# 1.net
KiCad netlist of a schematic drawn in EAGLE
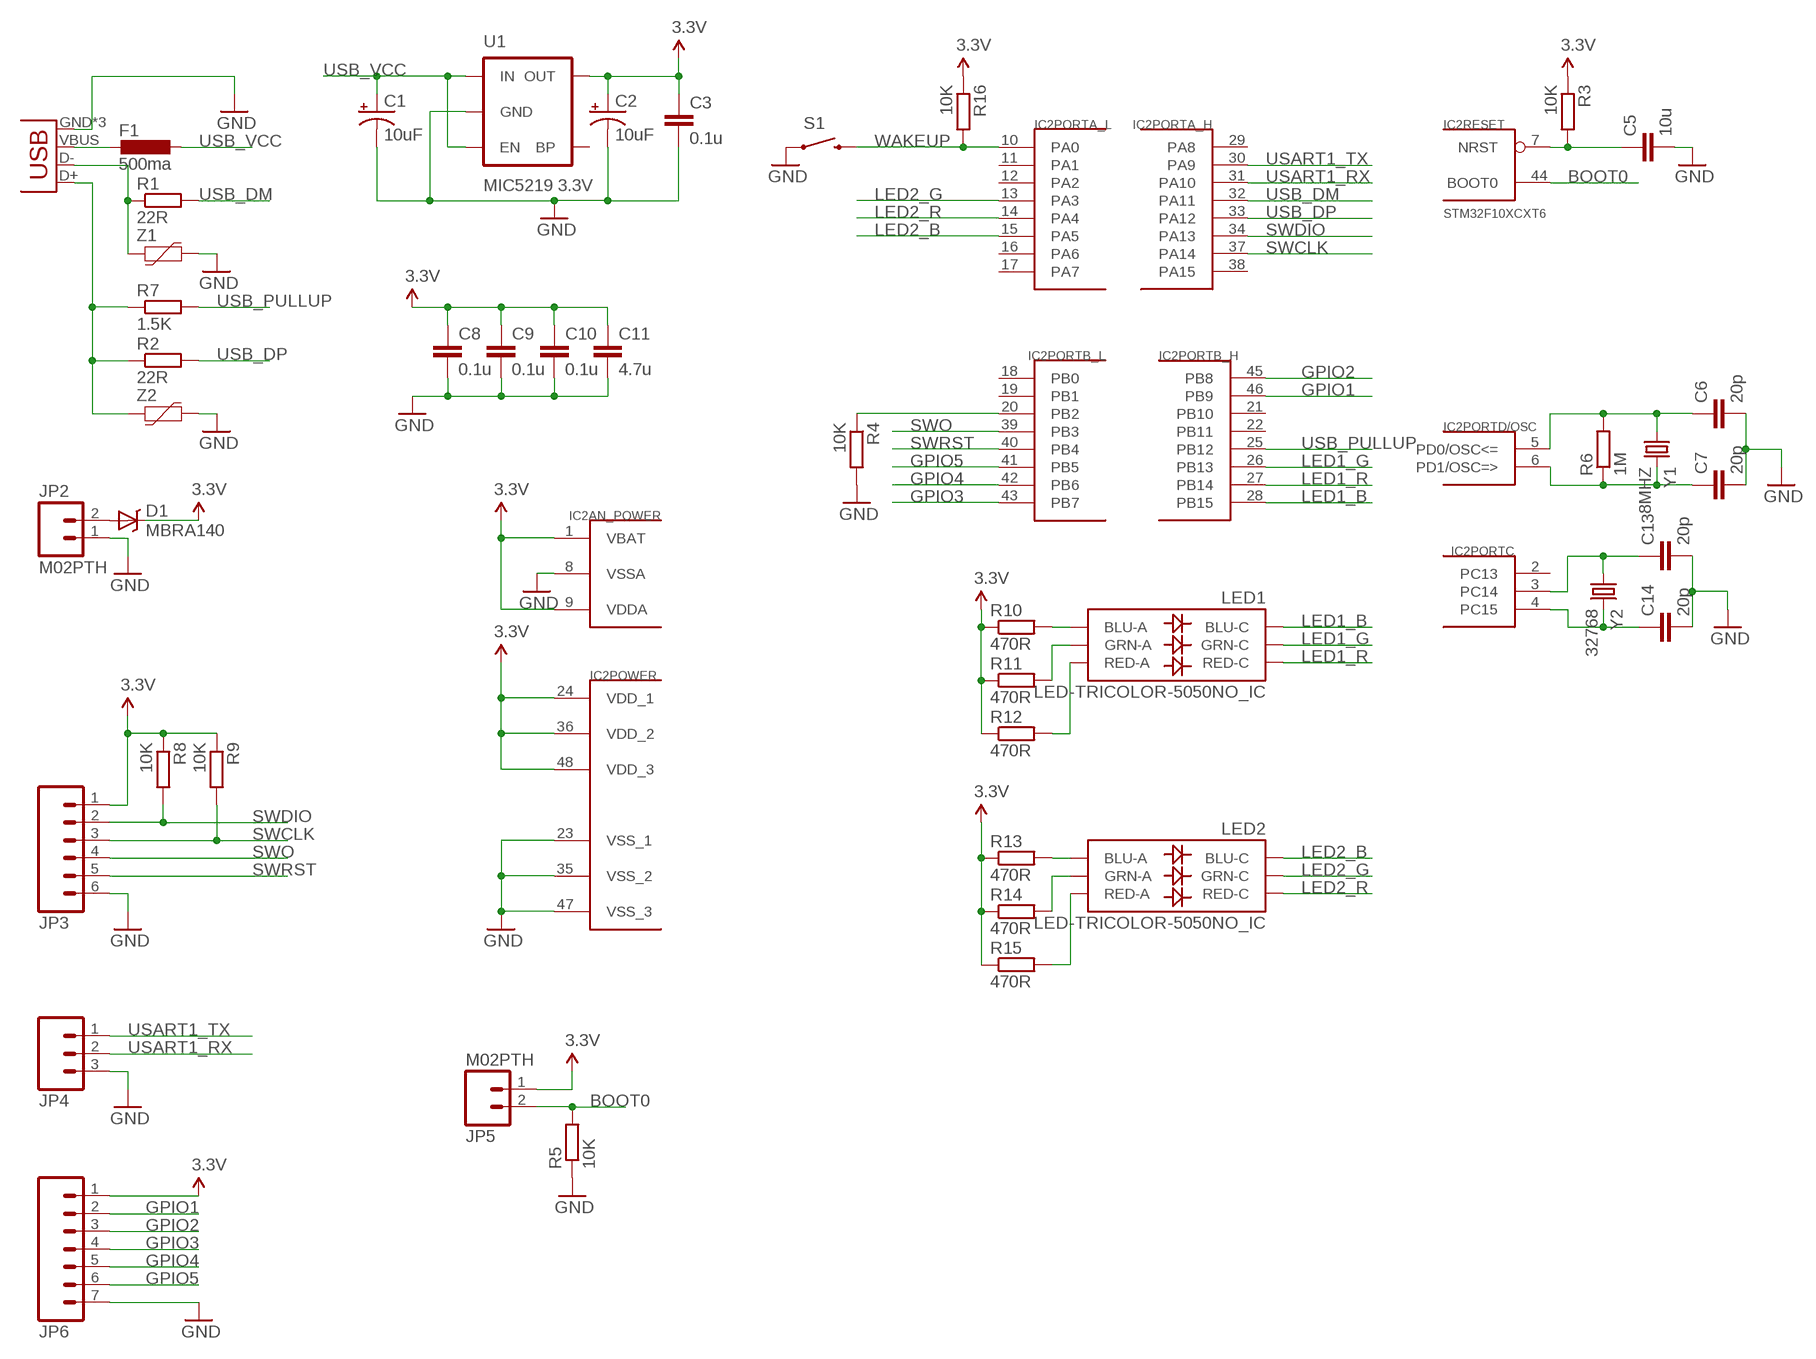
[diagram p0: schematic, sheet 1]

(export (version "E")
  (design (tool "Eeschema 10.0.6"))
  (components
    (comp (ref "C1")
      (value "10uF")
      (footprint "eagle-import:EIA3216")
      (libsource (lib "eagle-import") (part "10UF-TANT"))
    )
    (comp (ref "C2")
      (value "10uF")
      (footprint "eagle-import:EIA3216")
      (libsource (lib "eagle-import") (part "10UF-TANT"))
    )
    (comp (ref "C3")
      (value "0.1u")
      (footprint "eagle-import:C0603K")
      (libsource (lib "eagle-import") (part "C-EUC0603K"))
    )
    (comp (ref "C5")
      (value "10u")
      (footprint "eagle-import:C0603K")
      (libsource (lib "eagle-import") (part "C-EUC0603K"))
    )
    (comp (ref "C6")
      (value "20p")
      (footprint "eagle-import:C0603K")
      (libsource (lib "eagle-import") (part "C-EUC0603K"))
    )
    (comp (ref "C7")
      (value "20p")
      (footprint "eagle-import:C0603K")
      (libsource (lib "eagle-import") (part "C-EUC0603K"))
    )
    (comp (ref "C8")
      (value "0.1u")
      (footprint "eagle-import:C0603K")
      (libsource (lib "eagle-import") (part "C-EUC0603K"))
    )
    (comp (ref "C9")
      (value "0.1u")
      (footprint "eagle-import:C0603K")
      (libsource (lib "eagle-import") (part "C-EUC0603K"))
    )
    (comp (ref "C10")
      (value "0.1u")
      (footprint "eagle-import:C0603K")
      (libsource (lib "eagle-import") (part "C-EUC0603K"))
    )
    (comp (ref "C11")
      (value "4.7u")
      (footprint "eagle-import:C0603K")
      (libsource (lib "eagle-import") (part "C-EUC0603K"))
    )
    (comp (ref "C13")
      (value "20p")
      (footprint "eagle-import:C0603K")
      (libsource (lib "eagle-import") (part "C-EUC0603K"))
    )
    (comp (ref "C14")
      (value "20p")
      (footprint "eagle-import:C0603K")
      (libsource (lib "eagle-import") (part "C-EUC0603K"))
    )
    (comp (ref "D1")
      (value "MBRA140")
      (footprint "eagle-import:SMA-DIODE")
      (libsource (lib "eagle-import") (part "MBRA140"))
    )
    (comp (ref "F1")
      (value "500ma")
      (footprint "eagle-import:L2012C")
      (libsource (lib "eagle-import") (part "L-EUL2012C"))
    )
    (comp (ref "IC2")
      (value "STM32F10XCXT6")
      (footprint "eagle-import:TQFP48")
      (libsource (lib "eagle-import") (part "STM32F10XCXT6"))
    )
    (comp (ref "JP1")
      (value "USB-MICROB")
      (footprint "eagle-import:USB-MICROB")
      (libsource (lib "eagle-import") (part "USB-MICROB"))
    )
    (comp (ref "JP2")
      (value "M02PTH")
      (footprint "eagle-import:1X02")
      (libsource (lib "eagle-import") (part "M02PTH"))
    )
    (comp (ref "JP3")
      (value "M06SIP")
      (footprint "eagle-import:1X06")
      (libsource (lib "eagle-import") (part "M06SIP"))
    )
    (comp (ref "JP4")
      (value "M03PTH")
      (footprint "eagle-import:1X03")
      (libsource (lib "eagle-import") (part "M03PTH"))
    )
    (comp (ref "JP5")
      (value "M02PTH")
      (footprint "eagle-import:1X02")
      (libsource (lib "eagle-import") (part "M02PTH"))
    )
    (comp (ref "JP6")
      (value "M07")
      (footprint "eagle-import:1X07")
      (libsource (lib "eagle-import") (part "M07"))
    )
    (comp (ref "LED1")
      (value "LED-TRICOLOR-5050NO_IC")
      (footprint "eagle-import:LED-TRICOLOR-5050")
      (libsource (lib "eagle-import") (part "LED-TRICOLOR-5050NO_IC"))
    )
    (comp (ref "LED2")
      (value "LED-TRICOLOR-5050NO_IC")
      (footprint "eagle-import:LED-TRICOLOR-5050")
      (libsource (lib "eagle-import") (part "LED-TRICOLOR-5050NO_IC"))
    )
    (comp (ref "R1")
      (value "22R")
      (footprint "eagle-import:R0603")
      (libsource (lib "eagle-import") (part "R-EU_R0603"))
    )
    (comp (ref "R2")
      (value "22R")
      (footprint "eagle-import:R0603")
      (libsource (lib "eagle-import") (part "R-EU_R0603"))
    )
    (comp (ref "R3")
      (value "10K")
      (footprint "eagle-import:R0603")
      (libsource (lib "eagle-import") (part "R-EU_R0603"))
    )
    (comp (ref "R4")
      (value "10K")
      (footprint "eagle-import:R0603")
      (libsource (lib "eagle-import") (part "R-EU_R0603"))
    )
    (comp (ref "R5")
      (value "10K")
      (footprint "eagle-import:R0603")
      (libsource (lib "eagle-import") (part "R-EU_R0603"))
    )
    (comp (ref "R6")
      (value "1M")
      (footprint "eagle-import:R0603")
      (libsource (lib "eagle-import") (part "R-EU_R0603"))
    )
    (comp (ref "R7")
      (value "1.5K")
      (footprint "eagle-import:R0603")
      (libsource (lib "eagle-import") (part "R-EU_R0603"))
    )
    (comp (ref "R8")
      (value "10K")
      (footprint "eagle-import:R0603")
      (libsource (lib "eagle-import") (part "R-EU_R0603"))
    )
    (comp (ref "R9")
      (value "10K")
      (footprint "eagle-import:R0603")
      (libsource (lib "eagle-import") (part "R-EU_R0603"))
    )
    (comp (ref "R10")
      (value "470R")
      (footprint "eagle-import:R0603")
      (libsource (lib "eagle-import") (part "R-EU_R0603"))
    )
    (comp (ref "R11")
      (value "470R")
      (footprint "eagle-import:R0603")
      (libsource (lib "eagle-import") (part "R-EU_R0603"))
    )
    (comp (ref "R12")
      (value "470R")
      (footprint "eagle-import:R0603")
      (libsource (lib "eagle-import") (part "R-EU_R0603"))
    )
    (comp (ref "R13")
      (value "470R")
      (footprint "eagle-import:R0603")
      (libsource (lib "eagle-import") (part "R-EU_R0603"))
    )
    (comp (ref "R14")
      (value "470R")
      (footprint "eagle-import:R0603")
      (libsource (lib "eagle-import") (part "R-EU_R0603"))
    )
    (comp (ref "R15")
      (value "470R")
      (footprint "eagle-import:R0603")
      (libsource (lib "eagle-import") (part "R-EU_R0603"))
    )
    (comp (ref "R16")
      (value "10K")
      (footprint "eagle-import:R0603")
      (libsource (lib "eagle-import") (part "R-EU_R0603"))
    )
    (comp (ref "S1")
      (value "SWITCH-MOMENTARY-2SMD-4")
      (footprint "eagle-import:TACTILE_SWITCH_TALL")
      (libsource (lib "eagle-import") (part "SWITCH-MOMENTARY-2SMD-4"))
    )
    (comp (ref "U1")
      (value "MIC5219 3.3V")
      (footprint "eagle-import:SOT23-5")
      (libsource (lib "eagle-import") (part "V_REG_MIC52193.3V"))
    )
    (comp (ref "Y1")
      (value "8MHZ")
      (footprint "eagle-import:CRYSTAL-SMD-5X3")
      (libsource (lib "eagle-import") (part "CRYSTAL5X3"))
    )
    (comp (ref "Y2")
      (value "32768")
      (footprint "eagle-import:CRYSTAL-32KHZ-SMD_EPSON_MC146")
      (libsource (lib "eagle-import") (part "CRYSTALEPSONMC146"))
    )
    (comp (ref "Z1")
      (value "VARISTOR-0603")
      (footprint "eagle-import:0603-RES")
      (libsource (lib "eagle-import") (part "VARISTOR-0603"))
    )
    (comp (ref "Z2")
      (value "VARISTOR-0603")
      (footprint "eagle-import:0603-RES")
      (libsource (lib "eagle-import") (part "VARISTOR-0603"))
    )
  )
  (nets
    (net (code "1") (name "/BOOT0") (class "Default")
      (node (ref "IC2") (pin "44") (pinfunction "BOOT0_44") (pintype "input"))
      (node (ref "JP5") (pin "2") (pinfunction "2_2") (pintype "passive"))
      (node (ref "R5") (pin "2") (pinfunction "2_2") (pintype "passive"))
    )
    (net (code "2") (name "/GPIO1") (class "Default")
      (node (ref "IC2") (pin "46") (pinfunction "PB9_46") (pintype "bidirectional"))
      (node (ref "JP6") (pin "2") (pinfunction "2_2") (pintype "passive"))
    )
    (net (code "3") (name "/GPIO2") (class "Default")
      (node (ref "IC2") (pin "45") (pinfunction "PB8_45") (pintype "bidirectional"))
      (node (ref "JP6") (pin "3") (pinfunction "3_3") (pintype "passive"))
    )
    (net (code "4") (name "/GPIO3") (class "Default")
      (node (ref "IC2") (pin "43") (pinfunction "PB7_43") (pintype "bidirectional"))
      (node (ref "JP6") (pin "4") (pinfunction "4_4") (pintype "passive"))
    )
    (net (code "5") (name "/GPIO4") (class "Default")
      (node (ref "IC2") (pin "42") (pinfunction "PB6_42") (pintype "bidirectional"))
      (node (ref "JP6") (pin "5") (pinfunction "5_5") (pintype "passive"))
    )
    (net (code "6") (name "/GPIO5") (class "Default")
      (node (ref "IC2") (pin "41") (pinfunction "PB5_41") (pintype "bidirectional"))
      (node (ref "JP6") (pin "6") (pinfunction "6_6") (pintype "passive"))
    )
    (net (code "7") (name "/LED1_B") (class "Default")
      (node (ref "IC2") (pin "28") (pinfunction "PB15_28") (pintype "bidirectional"))
      (node (ref "LED1") (pin "4") (pinfunction "BLU-C_4") (pintype "bidirectional"))
    )
    (net (code "8") (name "/LED1_G") (class "Default")
      (node (ref "IC2") (pin "26") (pinfunction "PB13_26") (pintype "bidirectional"))
      (node (ref "LED1") (pin "6") (pinfunction "GRN-C_6") (pintype "bidirectional"))
    )
    (net (code "9") (name "/LED1_R") (class "Default")
      (node (ref "IC2") (pin "27") (pinfunction "PB14_27") (pintype "bidirectional"))
      (node (ref "LED1") (pin "5") (pinfunction "RED-C_5") (pintype "bidirectional"))
    )
    (net (code "10") (name "/LED2_B") (class "Default")
      (node (ref "IC2") (pin "15") (pinfunction "PA5_15") (pintype "bidirectional"))
      (node (ref "LED2") (pin "4") (pinfunction "BLU-C_4") (pintype "bidirectional"))
    )
    (net (code "11") (name "/LED2_G") (class "Default")
      (node (ref "IC2") (pin "13") (pinfunction "PA3_13") (pintype "bidirectional"))
      (node (ref "LED2") (pin "6") (pinfunction "GRN-C_6") (pintype "bidirectional"))
    )
    (net (code "12") (name "/LED2_R") (class "Default")
      (node (ref "IC2") (pin "14") (pinfunction "PA4_14") (pintype "bidirectional"))
      (node (ref "LED2") (pin "5") (pinfunction "RED-C_5") (pintype "bidirectional"))
    )
    (net (code "13") (name "/SWCLK") (class "Default")
      (node (ref "IC2") (pin "37") (pinfunction "PA14_37") (pintype "bidirectional"))
      (node (ref "JP3") (pin "3") (pinfunction "3_3") (pintype "passive"))
      (node (ref "R9") (pin "2") (pinfunction "2_2") (pintype "passive"))
    )
    (net (code "14") (name "/SWDIO") (class "Default")
      (node (ref "IC2") (pin "34") (pinfunction "PA13_34") (pintype "bidirectional"))
      (node (ref "JP3") (pin "2") (pinfunction "2_2") (pintype "passive"))
      (node (ref "R8") (pin "2") (pinfunction "2_2") (pintype "passive"))
    )
    (net (code "15") (name "/SWO") (class "Default")
      (node (ref "IC2") (pin "39") (pinfunction "PB3_39") (pintype "bidirectional"))
      (node (ref "JP3") (pin "4") (pinfunction "4_4") (pintype "passive"))
    )
    (net (code "16") (name "/SWRST") (class "Default")
      (node (ref "IC2") (pin "40") (pinfunction "PB4_40") (pintype "bidirectional"))
      (node (ref "JP3") (pin "5") (pinfunction "5_5") (pintype "passive"))
    )
    (net (code "17") (name "/USART1_RX") (class "Default")
      (node (ref "IC2") (pin "31") (pinfunction "PA10_31") (pintype "bidirectional"))
      (node (ref "JP4") (pin "2") (pinfunction "2_2") (pintype "passive"))
    )
    (net (code "18") (name "/USART1_TX") (class "Default")
      (node (ref "IC2") (pin "30") (pinfunction "PA9_30") (pintype "bidirectional"))
      (node (ref "JP4") (pin "1") (pinfunction "1_1") (pintype "passive"))
    )
    (net (code "19") (name "/USB_DM") (class "Default")
      (node (ref "IC2") (pin "32") (pinfunction "PA11_32") (pintype "bidirectional"))
      (node (ref "R1") (pin "2") (pinfunction "2_2") (pintype "passive"))
    )
    (net (code "20") (name "/USB_DP") (class "Default")
      (node (ref "IC2") (pin "33") (pinfunction "PA12_33") (pintype "bidirectional"))
      (node (ref "R2") (pin "2") (pinfunction "2_2") (pintype "passive"))
    )
    (net (code "21") (name "/USB_PULLUP") (class "Default")
      (node (ref "IC2") (pin "25") (pinfunction "PB12_25") (pintype "bidirectional"))
      (node (ref "R7") (pin "2") (pinfunction "2_2") (pintype "passive"))
    )
    (net (code "22") (name "/USB_VCC") (class "Default")
      (node (ref "C1") (pin "A") (pinfunction "+_A") (pintype "passive"))
      (node (ref "F1") (pin "1") (pinfunction "1_1") (pintype "passive"))
      (node (ref "U1") (pin "1") (pinfunction "IN_1") (pintype "input"))
      (node (ref "U1") (pin "3") (pinfunction "EN_3") (pintype "input"))
    )
    (net (code "23") (name "/WAKEUP") (class "Default")
      (node (ref "IC2") (pin "10") (pinfunction "PA0_10") (pintype "bidirectional"))
      (node (ref "R16") (pin "2") (pinfunction "2_2") (pintype "passive"))
      (node (ref "S1") (pin "B2") (pinfunction "2_B2") (pintype "passive"))
    )
    (net (code "24") (name "3.3V") (class "Default")
      (node (ref "C10") (pin "1") (pinfunction "1_1") (pintype "passive"))
      (node (ref "C11") (pin "1") (pinfunction "1_1") (pintype "passive"))
      (node (ref "C2") (pin "A") (pinfunction "+_A") (pintype "passive"))
      (node (ref "C3") (pin "1") (pinfunction "1_1") (pintype "passive"))
      (node (ref "C8") (pin "1") (pinfunction "1_1") (pintype "passive"))
      (node (ref "C9") (pin "1") (pinfunction "1_1") (pintype "passive"))
      (node (ref "D1") (pin "C") (pinfunction "C_C") (pintype "passive"))
      (node (ref "IC2") (pin "1") (pinfunction "VBAT_1") (pintype "power_in"))
      (node (ref "IC2") (pin "24") (pinfunction "VDD_1_24") (pintype "power_in"))
      (node (ref "IC2") (pin "36") (pinfunction "VDD_2_36") (pintype "power_in"))
      (node (ref "IC2") (pin "48") (pinfunction "VDD_3_48") (pintype "power_in"))
      (node (ref "IC2") (pin "9") (pinfunction "VDDA_9") (pintype "power_in"))
      (node (ref "JP3") (pin "1") (pinfunction "1_1") (pintype "passive"))
      (node (ref "JP5") (pin "1") (pinfunction "1_1") (pintype "passive"))
      (node (ref "JP6") (pin "1") (pinfunction "1_1") (pintype "passive"))
      (node (ref "R10") (pin "1") (pinfunction "1_1") (pintype "passive"))
      (node (ref "R11") (pin "1") (pinfunction "1_1") (pintype "passive"))
      (node (ref "R12") (pin "1") (pinfunction "1_1") (pintype "passive"))
      (node (ref "R13") (pin "1") (pinfunction "1_1") (pintype "passive"))
      (node (ref "R14") (pin "1") (pinfunction "1_1") (pintype "passive"))
      (node (ref "R15") (pin "1") (pinfunction "1_1") (pintype "passive"))
      (node (ref "R16") (pin "1") (pinfunction "1_1") (pintype "passive"))
      (node (ref "R3") (pin "1") (pinfunction "1_1") (pintype "passive"))
      (node (ref "R8") (pin "1") (pinfunction "1_1") (pintype "passive"))
      (node (ref "R9") (pin "1") (pinfunction "1_1") (pintype "passive"))
      (node (ref "U1") (pin "5") (pinfunction "OUT_5") (pintype "passive"))
    )
    (net (code "25") (name "GND") (class "Default")
      (node (ref "C1") (pin "C") (pinfunction "-_C") (pintype "passive"))
      (node (ref "C10") (pin "2") (pinfunction "2_2") (pintype "passive"))
      (node (ref "C11") (pin "2") (pinfunction "2_2") (pintype "passive"))
      (node (ref "C13") (pin "2") (pinfunction "2_2") (pintype "passive"))
      (node (ref "C14") (pin "2") (pinfunction "2_2") (pintype "passive"))
      (node (ref "C2") (pin "C") (pinfunction "-_C") (pintype "passive"))
      (node (ref "C3") (pin "2") (pinfunction "2_2") (pintype "passive"))
      (node (ref "C5") (pin "2") (pinfunction "2_2") (pintype "passive"))
      (node (ref "C6") (pin "2") (pinfunction "2_2") (pintype "passive"))
      (node (ref "C7") (pin "2") (pinfunction "2_2") (pintype "passive"))
      (node (ref "C8") (pin "2") (pinfunction "2_2") (pintype "passive"))
      (node (ref "C9") (pin "2") (pinfunction "2_2") (pintype "passive"))
      (node (ref "IC2") (pin "23") (pinfunction "VSS_1_23") (pintype "power_in"))
      (node (ref "IC2") (pin "35") (pinfunction "VSS_2_35") (pintype "power_in"))
      (node (ref "IC2") (pin "47") (pinfunction "VSS_3_47") (pintype "power_in"))
      (node (ref "IC2") (pin "8") (pinfunction "VSSA_8") (pintype "power_in"))
      (node (ref "JP1") (pin "GND") (pinfunction "GND_GND") (pintype "bidirectional"))
      (node (ref "JP1") (pin "MT1") (pinfunction "GND_MT1") (pintype "bidirectional"))
      (node (ref "JP1") (pin "MT2") (pinfunction "GND_MT2") (pintype "bidirectional"))
      (node (ref "JP2") (pin "1") (pinfunction "1_1") (pintype "passive"))
      (node (ref "JP3") (pin "6") (pinfunction "6_6") (pintype "passive"))
      (node (ref "JP4") (pin "3") (pinfunction "3_3") (pintype "passive"))
      (node (ref "JP6") (pin "7") (pinfunction "7_7") (pintype "passive"))
      (node (ref "R4") (pin "2") (pinfunction "2_2") (pintype "passive"))
      (node (ref "R5") (pin "1") (pinfunction "1_1") (pintype "passive"))
      (node (ref "S1") (pin "A2") (pinfunction "1_A2") (pintype "passive"))
      (node (ref "U1") (pin "2") (pinfunction "GND_2") (pintype "input"))
      (node (ref "Z1") (pin "2") (pinfunction "2_2") (pintype "passive"))
      (node (ref "Z2") (pin "2") (pinfunction "2_2") (pintype "passive"))
    )
    (net (code "26") (name "Net-(D1-PadA)") (class "Default")
      (node (ref "D1") (pin "A") (pinfunction "A_A") (pintype "passive"))
      (node (ref "JP2") (pin "2") (pinfunction "2_2") (pintype "passive"))
    )
    (net (code "27") (name "Net-(F1-Pad2)") (class "Default")
      (node (ref "F1") (pin "2") (pinfunction "2_2") (pintype "passive"))
      (node (ref "JP1") (pin "VBUS") (pinfunction "VBUS_VBUS") (pintype "bidirectional"))
    )
    (net (code "28") (name "Net-(IC2E-PB2)") (class "Default")
      (node (ref "IC2") (pin "20") (pinfunction "PB2_20") (pintype "bidirectional"))
      (node (ref "R4") (pin "1") (pinfunction "1_1") (pintype "passive"))
    )
    (net (code "29") (name "Net-(IC2F-PC14)") (class "Default")
      (node (ref "C13") (pin "1") (pinfunction "1_1") (pintype "passive"))
      (node (ref "IC2") (pin "3") (pinfunction "PC14_3") (pintype "bidirectional"))
      (node (ref "Y2") (pin "P$2") (pinfunction "1_P$2") (pintype "passive"))
    )
    (net (code "30") (name "Net-(IC2F-PC15)") (class "Default")
      (node (ref "C14") (pin "1") (pinfunction "1_1") (pintype "passive"))
      (node (ref "IC2") (pin "4") (pinfunction "PC15_4") (pintype "bidirectional"))
      (node (ref "Y2") (pin "P$1") (pinfunction "2_P$1") (pintype "passive"))
    )
    (net (code "31") (name "Net-(IC2G-PD0{slash}OSC<=)") (class "Default")
      (node (ref "C6") (pin "1") (pinfunction "1_1") (pintype "passive"))
      (node (ref "IC2") (pin "5") (pinfunction "PD0/OSC<=_5") (pintype "bidirectional"))
      (node (ref "R6") (pin "2") (pinfunction "2_2") (pintype "passive"))
      (node (ref "Y1") (pin "1") (pinfunction "1_1") (pintype "passive"))
    )
    (net (code "32") (name "Net-(IC2G-PD1{slash}OSC=>)") (class "Default")
      (node (ref "C7") (pin "1") (pinfunction "1_1") (pintype "passive"))
      (node (ref "IC2") (pin "6") (pinfunction "PD1/OSC=>_6") (pintype "bidirectional"))
      (node (ref "R6") (pin "1") (pinfunction "1_1") (pintype "passive"))
      (node (ref "Y1") (pin "3") (pinfunction "2_3") (pintype "passive"))
    )
    (net (code "33") (name "Net-(IC2I-NRST)") (class "Default")
      (node (ref "C5") (pin "1") (pinfunction "1_1") (pintype "passive"))
      (node (ref "IC2") (pin "7") (pinfunction "NRST_7") (pintype "input"))
      (node (ref "R3") (pin "2") (pinfunction "2_2") (pintype "passive"))
    )
    (net (code "34") (name "Net-(JP1-PadD+)") (class "Default")
      (node (ref "JP1") (pin "D+") (pinfunction "D+_D+") (pintype "bidirectional"))
      (node (ref "R2") (pin "1") (pinfunction "1_1") (pintype "passive"))
      (node (ref "R7") (pin "1") (pinfunction "1_1") (pintype "passive"))
      (node (ref "Z2") (pin "1") (pinfunction "1_1") (pintype "passive"))
    )
    (net (code "35") (name "Net-(JP1-PadD-)") (class "Default")
      (node (ref "JP1") (pin "D-") (pinfunction "D-_D-") (pintype "bidirectional"))
      (node (ref "R1") (pin "1") (pinfunction "1_1") (pintype "passive"))
      (node (ref "Z1") (pin "1") (pinfunction "1_1") (pintype "passive"))
    )
    (net (code "36") (name "Net-(LED1-BLU-A)") (class "Default")
      (node (ref "LED1") (pin "3") (pinfunction "BLU-A_3") (pintype "bidirectional"))
      (node (ref "R10") (pin "2") (pinfunction "2_2") (pintype "passive"))
    )
    (net (code "37") (name "Net-(LED1-GRN-A)") (class "Default")
      (node (ref "LED1") (pin "1") (pinfunction "GRN-A_1") (pintype "bidirectional"))
      (node (ref "R11") (pin "2") (pinfunction "2_2") (pintype "passive"))
    )
    (net (code "38") (name "Net-(LED1-RED-A)") (class "Default")
      (node (ref "LED1") (pin "2") (pinfunction "RED-A_2") (pintype "bidirectional"))
      (node (ref "R12") (pin "2") (pinfunction "2_2") (pintype "passive"))
    )
    (net (code "39") (name "Net-(LED2-BLU-A)") (class "Default")
      (node (ref "LED2") (pin "3") (pinfunction "BLU-A_3") (pintype "bidirectional"))
      (node (ref "R13") (pin "2") (pinfunction "2_2") (pintype "passive"))
    )
    (net (code "40") (name "Net-(LED2-GRN-A)") (class "Default")
      (node (ref "LED2") (pin "1") (pinfunction "GRN-A_1") (pintype "bidirectional"))
      (node (ref "R14") (pin "2") (pinfunction "2_2") (pintype "passive"))
    )
    (net (code "41") (name "Net-(LED2-RED-A)") (class "Default")
      (node (ref "LED2") (pin "2") (pinfunction "RED-A_2") (pintype "bidirectional"))
      (node (ref "R15") (pin "2") (pinfunction "2_2") (pintype "passive"))
    )
    (net (code "42") (name "unconnected-(IC2B-PA8-Pad29)") (class "Default")
      (node (ref "IC2") (pin "29") (pinfunction "PA8_29") (pintype "bidirectional"))
    )
    (net (code "43") (name "unconnected-(IC2B-PA15-Pad38)") (class "Default")
      (node (ref "IC2") (pin "38") (pinfunction "PA15_38") (pintype "bidirectional"))
    )
    (net (code "44") (name "unconnected-(IC2C-PA1-Pad11)") (class "Default")
      (node (ref "IC2") (pin "11") (pinfunction "PA1_11") (pintype "bidirectional"))
    )
    (net (code "45") (name "unconnected-(IC2C-PA2-Pad12)") (class "Default")
      (node (ref "IC2") (pin "12") (pinfunction "PA2_12") (pintype "bidirectional"))
    )
    (net (code "46") (name "unconnected-(IC2C-PA6-Pad16)") (class "Default")
      (node (ref "IC2") (pin "16") (pinfunction "PA6_16") (pintype "bidirectional"))
    )
    (net (code "47") (name "unconnected-(IC2C-PA7-Pad17)") (class "Default")
      (node (ref "IC2") (pin "17") (pinfunction "PA7_17") (pintype "bidirectional"))
    )
    (net (code "48") (name "unconnected-(IC2D-PB10-Pad21)") (class "Default")
      (node (ref "IC2") (pin "21") (pinfunction "PB10_21") (pintype "bidirectional"))
    )
    (net (code "49") (name "unconnected-(IC2D-PB11-Pad22)") (class "Default")
      (node (ref "IC2") (pin "22") (pinfunction "PB11_22") (pintype "bidirectional"))
    )
    (net (code "50") (name "unconnected-(IC2E-PB0-Pad18)") (class "Default")
      (node (ref "IC2") (pin "18") (pinfunction "PB0_18") (pintype "bidirectional"))
    )
    (net (code "51") (name "unconnected-(IC2E-PB1-Pad19)") (class "Default")
      (node (ref "IC2") (pin "19") (pinfunction "PB1_19") (pintype "bidirectional"))
    )
    (net (code "52") (name "unconnected-(IC2F-PC13-Pad2)") (class "Default")
      (node (ref "IC2") (pin "2") (pinfunction "PC13_2") (pintype "bidirectional"))
    )
    (net (code "53") (name "unconnected-(U1-BP-Pad4)") (class "Default")
      (node (ref "U1") (pin "4") (pinfunction "BP_4") (pintype "input"))
    )
  )
)
